# MECHANICAL.net
KiCad netlist of a schematic drawn in Altium Designer
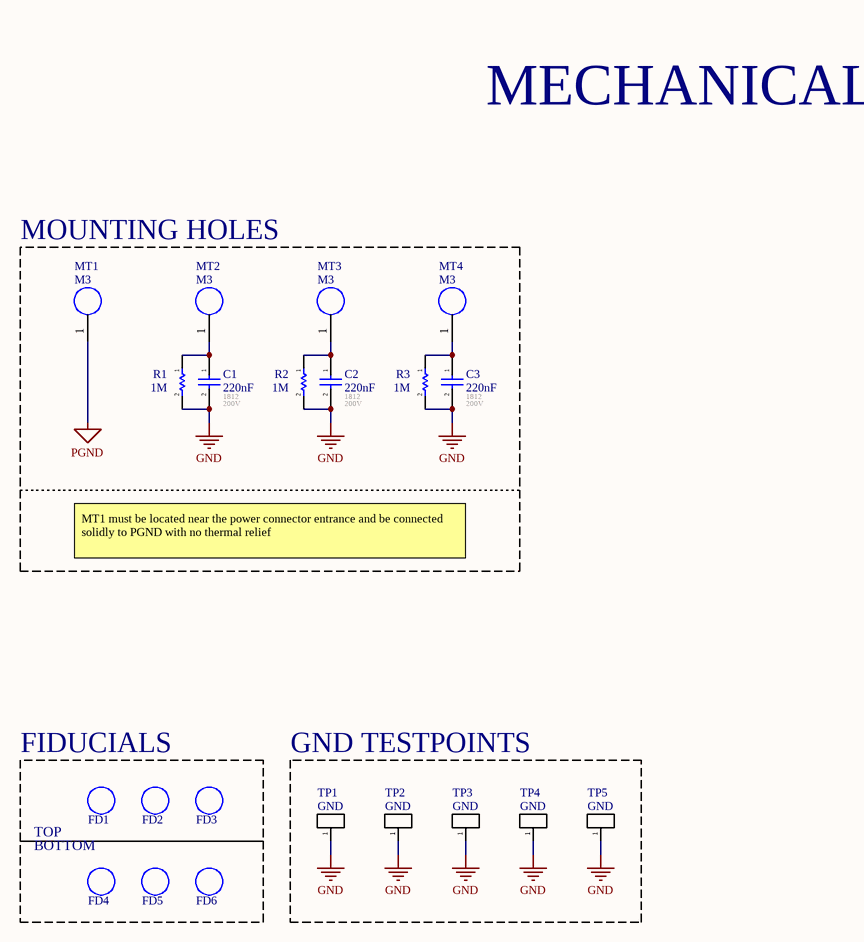
[diagram p0: MECHANICAL.SchDoc]

(export (version "E")
  (design (tool "Eeschema 10.0.6"))
  (components
    (comp (ref "C1")
      (value "220nF")
      (footprint "1812")
      (description "Generic SMT Ceramic Capacitor")
      (fields (field (name "VOLTAGE - RATED") "200V"))
      (libsource (lib "Symbols") (part "CAP_CER"))
    )
    (comp (ref "C2")
      (value "220nF")
      (footprint "1812")
      (description "Generic SMT Ceramic Capacitor")
      (fields (field (name "VOLTAGE - RATED") "200V"))
      (libsource (lib "Symbols") (part "CAP_CER"))
    )
    (comp (ref "C3")
      (value "220nF")
      (footprint "1812")
      (description "Generic SMT Ceramic Capacitor")
      (fields (field (name "VOLTAGE - RATED") "200V"))
      (libsource (lib "Symbols") (part "CAP_CER"))
    )
    (comp (ref "FD1") (value "FIDUCIAL") (footprint "FIDUCIAL") (libsource (lib "Symbols") (part "FIDUCIAL")))
    (comp (ref "FD2") (value "FIDUCIAL") (footprint "FIDUCIAL") (libsource (lib "Symbols") (part "FIDUCIAL")))
    (comp (ref "FD3") (value "FIDUCIAL") (footprint "FIDUCIAL") (libsource (lib "Symbols") (part "FIDUCIAL")))
    (comp (ref "FD4") (value "FIDUCIAL") (footprint "FIDUCIAL") (libsource (lib "Symbols") (part "FIDUCIAL")))
    (comp (ref "FD5") (value "FIDUCIAL") (footprint "FIDUCIAL") (libsource (lib "Symbols") (part "FIDUCIAL")))
    (comp (ref "FD6") (value "FIDUCIAL") (footprint "FIDUCIAL") (libsource (lib "Symbols") (part "FIDUCIAL")))
    (comp (ref "MT1") (value "M3") (footprint "MTH_M3") (libsource (lib "RaesLib") (part "MOUNTING_HOLE")))
    (comp (ref "MT2") (value "M3") (footprint "MTH_M3") (libsource (lib "RaesLib") (part "MOUNTING_HOLE")))
    (comp (ref "MT3") (value "M3") (footprint "MTH_M3") (libsource (lib "RaesLib") (part "MOUNTING_HOLE")))
    (comp (ref "MT4") (value "M3") (footprint "MTH_M3") (libsource (lib "RaesLib") (part "MOUNTING_HOLE")))
    (comp (ref "R1")
      (value "1M")
      (footprint "RES_0402")
      (description "Resistor")
      (fields (field (name "POWER") "1/16W") (field (name "TOLERANCE") "10%"))
      (libsource (lib "Symbols") (part "RESISTOR"))
    )
    (comp (ref "R2")
      (value "1M")
      (footprint "RES_0402")
      (description "Resistor")
      (fields (field (name "POWER") "1/16W") (field (name "TOLERANCE") "10%"))
      (libsource (lib "Symbols") (part "RESISTOR"))
    )
    (comp (ref "R3")
      (value "1M")
      (footprint "RES_0402")
      (description "Resistor")
      (fields (field (name "POWER") "1/16W") (field (name "TOLERANCE") "10%"))
      (libsource (lib "Symbols") (part "RESISTOR"))
    )
    (comp (ref "TP1")
      (value "GND")
      (footprint "TP_HOLE")
      (description "Test Point")
      (libsource (lib "Symbols") (part "TESTPOINT"))
    )
    (comp (ref "TP2")
      (value "GND")
      (footprint "TP_HOLE")
      (description "Test Point")
      (libsource (lib "Symbols") (part "TESTPOINT"))
    )
    (comp (ref "TP3")
      (value "GND")
      (footprint "TP_HOLE")
      (description "Test Point")
      (libsource (lib "Symbols") (part "TESTPOINT"))
    )
    (comp (ref "TP4")
      (value "GND")
      (footprint "TP_HOLE")
      (description "Test Point")
      (libsource (lib "Symbols") (part "TESTPOINT"))
    )
    (comp (ref "TP5")
      (value "GND")
      (footprint "TP_HOLE")
      (description "Test Point")
      (libsource (lib "Symbols") (part "TESTPOINT"))
    )
  )
  (nets
    (net (code "1") (name "GND") (class "Default")
      (node (ref "C1") (pin "2") (pinfunction "2_2") (pintype "passive"))
      (node (ref "C2") (pin "2") (pinfunction "2_2") (pintype "passive"))
      (node (ref "C3") (pin "2") (pinfunction "2_2") (pintype "passive"))
      (node (ref "R1") (pin "2") (pinfunction "2_2") (pintype "passive"))
      (node (ref "R2") (pin "2") (pinfunction "2_2") (pintype "passive"))
      (node (ref "R3") (pin "2") (pinfunction "2_2") (pintype "passive"))
      (node (ref "TP1") (pin "1") (pinfunction "A_1") (pintype "passive"))
      (node (ref "TP2") (pin "1") (pinfunction "A_1") (pintype "passive"))
      (node (ref "TP3") (pin "1") (pinfunction "A_1") (pintype "passive"))
      (node (ref "TP4") (pin "1") (pinfunction "A_1") (pintype "passive"))
      (node (ref "TP5") (pin "1") (pinfunction "A_1") (pintype "passive"))
    )
    (net (code "2") (name "Net-(C1-Pad1)") (class "Default")
      (node (ref "C1") (pin "1") (pinfunction "1_1") (pintype "passive"))
      (node (ref "MT2") (pin "1") (pintype "passive"))
      (node (ref "R1") (pin "1") (pinfunction "1_1") (pintype "passive"))
    )
    (net (code "3") (name "Net-(C2-Pad1)") (class "Default")
      (node (ref "C2") (pin "1") (pinfunction "1_1") (pintype "passive"))
      (node (ref "MT3") (pin "1") (pintype "passive"))
      (node (ref "R2") (pin "1") (pinfunction "1_1") (pintype "passive"))
    )
    (net (code "4") (name "Net-(C3-Pad1)") (class "Default")
      (node (ref "C3") (pin "1") (pinfunction "1_1") (pintype "passive"))
      (node (ref "MT4") (pin "1") (pintype "passive"))
      (node (ref "R3") (pin "1") (pinfunction "1_1") (pintype "passive"))
    )
    (net (code "5") (name "PGND") (class "Default") (node (ref "MT1") (pin "1") (pintype "passive")))
  )
)
